# Turbidity_V2.net
KiCad netlist of a schematic drawn in Altium Designer
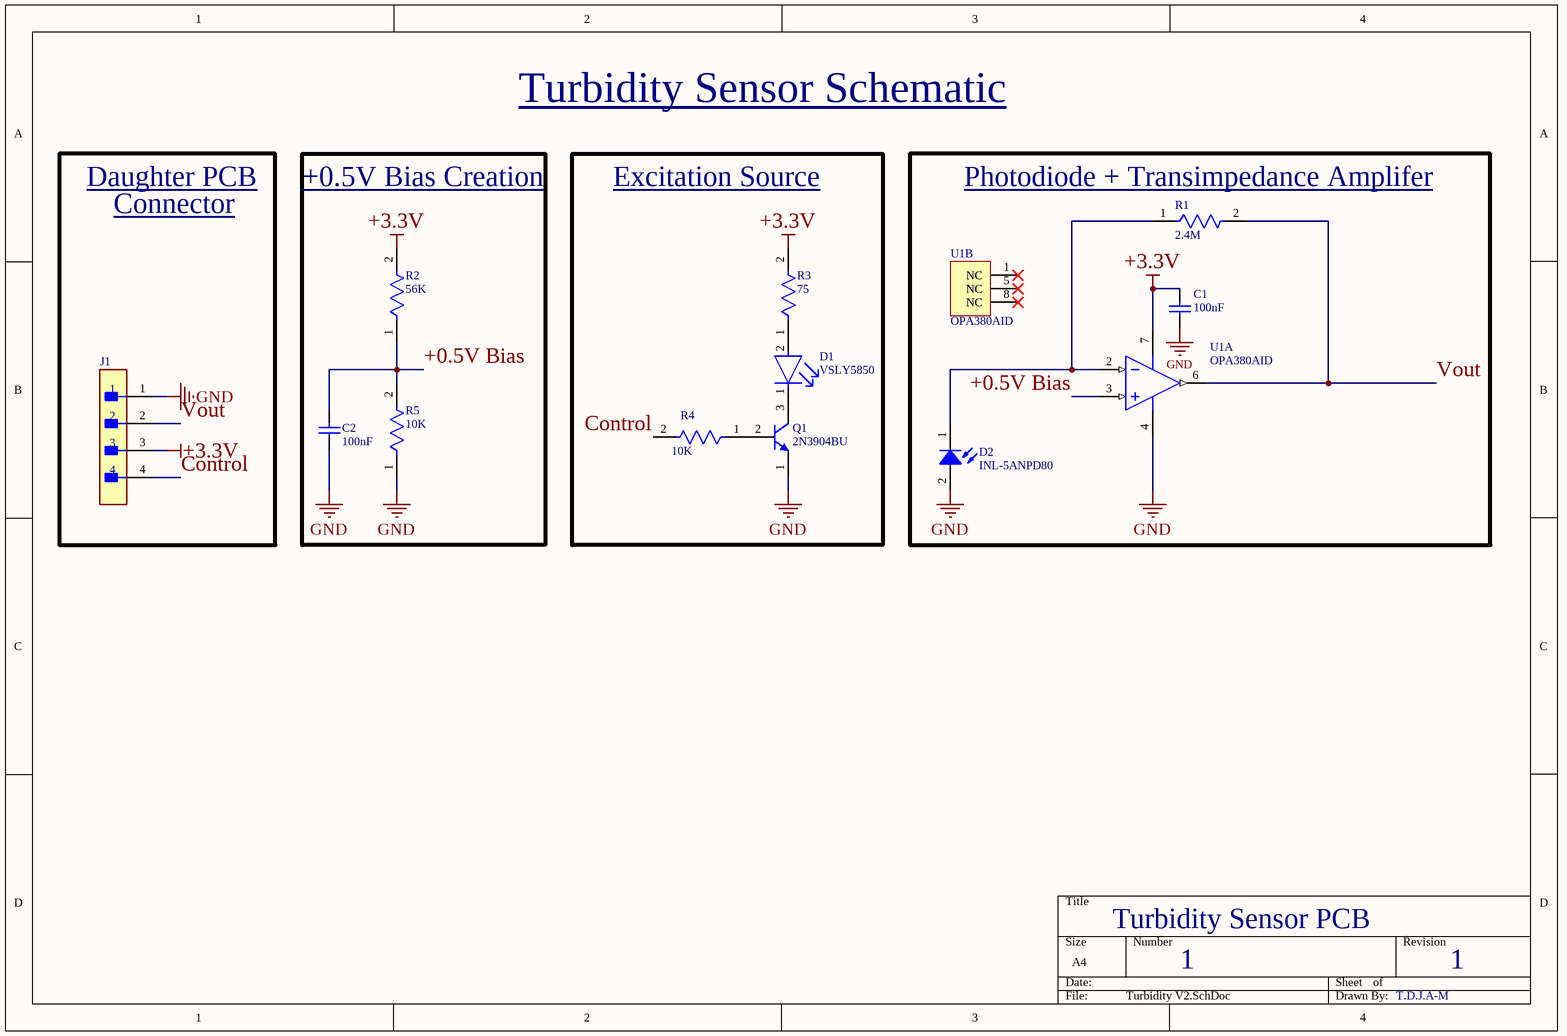
[diagram p0: Turbidity V2.SchDoc]

(export (version "E")
  (design (tool "Eeschema 10.0.6"))
  (components
    (comp (ref "C1")
      (value "100nF")
      (footprint "CAPC2013X145X48ML20T23")
      (fields (field (name "MANUFACTURER") "Vitramon") (field (name "PART NUMBER") "VJ0805Y682KXAMT"))
      (libsource (lib "Altium Content Vault") (part "CAP"))
    )
    (comp (ref "C2")
      (value "100nF")
      (footprint "CAPC2013X145X48ML20T23")
      (fields (field (name "MANUFACTURER") "Vitramon") (field (name "PART NUMBER") "VJ0805Y682KXAMT"))
      (libsource (lib "Altium Content Vault") (part "CAP"))
    )
    (comp (ref "D1")
      (value "VSLY5850")
      (footprint "FP-XLUR12D-MFG")
      (description "627nm Red LED; 5x8.6mm, Through-Hole Mount with Red Diffused Round Lamp")
      (libsource (lib "Altium Content Vault") (part "XLUR12D"))
    )
    (comp (ref "D2")
      (value "INL-5ANPD80")
      (footprint "WL-TDRW_D5.8H8.7")
      (description "1540051EA3590 WL-TDRW THT Photodiode Round Waterclear")
      (libsource (lib "Altium Content Vault") (part "Photodiode"))
    )
    (comp (ref "J1")
      (value "~")
      (footprint "FP-22-29-2041-MFG")
      (description "CONN HEADER VERT 4POS 2.54MM")
      (libsource (lib "Altium Content Vault") (part "299a8cea1bdcbc3624fe62c390fa72c"))
    )
    (comp (ref "Q1")
      (value "2N3904BU")
      (footprint "FAIR-TO-92")
      (description "NPN General-Purpose Amplifier, 40 V VCEO, 0.2 A, -55 to 150 degC, 2-Pin TO-92, RoHS, Bulk")
      (fields (field (name "MANUFACTURER") "FairchildSemiconductor"))
      (libsource (lib "Altium Content Vault") (part "NPN-E1B2C3-3"))
    )
    (comp (ref "R1")
      (value "2.4M")
      (footprint "FP-RT0805-IPC_A")
      (description "RES SMD 681 OHM 0.1% 1/8W 0805")
      (fields
        (field (name "MANUFACTURER") "Yageo")
        (field (name "MANUFACTURER PART NUMBER") "RT0805BRD07681RL")
      )
      (libsource (lib "Altium Content Vault") (part "1029c3af85768c4190bb7ad29bc67b5"))
    )
    (comp (ref "R2")
      (value "56K")
      (footprint "FP-RT0805-IPC_A")
      (description "RES SMD 681 OHM 0.1% 1/8W 0805")
      (fields
        (field (name "MANUFACTURER") "Yageo")
        (field (name "MANUFACTURER PART NUMBER") "RT0805BRD07681RL")
      )
      (libsource (lib "Altium Content Vault") (part "1029c3af85768c4190bb7ad29bc67b5"))
    )
    (comp (ref "R3")
      (value "75")
      (footprint "FP-RT0805-IPC_A")
      (description "RES SMD 681 OHM 0.1% 1/8W 0805")
      (fields
        (field (name "MANUFACTURER") "Yageo")
        (field (name "MANUFACTURER PART NUMBER") "RT0805BRD07681RL")
      )
      (libsource (lib "Altium Content Vault") (part "1029c3af85768c4190bb7ad29bc67b5"))
    )
    (comp (ref "R4")
      (value "10K")
      (footprint "FP-RT0805-IPC_A")
      (description "RES SMD 681 OHM 0.1% 1/8W 0805")
      (fields
        (field (name "MANUFACTURER") "Yageo")
        (field (name "MANUFACTURER PART NUMBER") "RT0805BRD07681RL")
      )
      (libsource (lib "Altium Content Vault") (part "1029c3af85768c4190bb7ad29bc67b5"))
    )
    (comp (ref "R5")
      (value "10K")
      (footprint "FP-RT0805-IPC_A")
      (description "RES SMD 681 OHM 0.1% 1/8W 0805")
      (fields
        (field (name "MANUFACTURER") "Yageo")
        (field (name "MANUFACTURER PART NUMBER") "RT0805BRD07681RL")
      )
      (libsource (lib "Altium Content Vault") (part "1029c3af85768c4190bb7ad29bc67b5"))
    )
    (comp (ref "U1")
      (value "OPA380AID")
      (footprint "D0008A_L")
      (fields (field (name "MANUFACTURER") "Texas Instruments"))
      (libsource (lib "Altium Content Vault") (part "TI-AMP-S3-2-8_B"))
    )
  )
  (nets
    (net (code "1") (name "+3.3V") (class "Default")
      (node (ref "C1") (pin "2") (pinfunction "2_2") (pintype "passive"))
      (node (ref "J1") (pin "3") (pinfunction "3_3") (pintype "passive"))
      (node (ref "R2") (pin "2") (pinfunction "2_2") (pintype "passive"))
      (node (ref "R3") (pin "2") (pinfunction "2_2") (pintype "passive"))
      (node (ref "U1") (pin "7") (pinfunction "V+_7") (pintype "power_in"))
    )
    (net (code "2") (name "/+0.5V Bias") (class "Default")
      (node (ref "C2") (pin "2") (pinfunction "2_2") (pintype "passive"))
      (node (ref "R2") (pin "1") (pinfunction "1_1") (pintype "passive"))
      (node (ref "R5") (pin "2") (pinfunction "2_2") (pintype "passive"))
      (node (ref "U1") (pin "3") (pinfunction "IN+_3") (pintype "input"))
    )
    (net (code "3") (name "/Control") (class "Default")
      (node (ref "J1") (pin "4") (pinfunction "4_4") (pintype "passive"))
      (node (ref "R4") (pin "2") (pinfunction "2_2") (pintype "passive"))
    )
    (net (code "4") (name "/Vout") (class "Default")
      (node (ref "J1") (pin "2") (pinfunction "2_2") (pintype "passive"))
      (node (ref "R1") (pin "2") (pinfunction "2_2") (pintype "passive"))
      (node (ref "U1") (pin "6") (pinfunction "OUT_6") (pintype "output"))
    )
    (net (code "5") (name "GND") (class "Default")
      (node (ref "C1") (pin "1") (pinfunction "1_1") (pintype "passive"))
      (node (ref "C2") (pin "1") (pinfunction "1_1") (pintype "passive"))
      (node (ref "D2") (pin "2") (pinfunction "A_2") (pintype "passive"))
      (node (ref "J1") (pin "1") (pinfunction "1_1") (pintype "passive"))
      (node (ref "Q1") (pin "1") (pinfunction "E_1") (pintype "passive"))
      (node (ref "R5") (pin "1") (pinfunction "1_1") (pintype "passive"))
      (node (ref "U1") (pin "4") (pinfunction "V-_4") (pintype "power_in"))
    )
    (net (code "6") (name "Net-(D1-A)") (class "Default")
      (node (ref "D1") (pin "2") (pinfunction "A_2") (pintype "passive"))
      (node (ref "R3") (pin "1") (pinfunction "1_1") (pintype "passive"))
    )
    (net (code "7") (name "Net-(D1-C)") (class "Default")
      (node (ref "D1") (pin "1") (pinfunction "C_1") (pintype "passive"))
      (node (ref "Q1") (pin "3") (pinfunction "C_3") (pintype "passive"))
    )
    (net (code "8") (name "Net-(D2-K)") (class "Default")
      (node (ref "D2") (pin "1") (pinfunction "K_1") (pintype "passive"))
      (node (ref "R1") (pin "1") (pinfunction "1_1") (pintype "passive"))
      (node (ref "U1") (pin "2") (pinfunction "IN-_2") (pintype "input"))
    )
    (net (code "9") (name "Net-(Q1-B)") (class "Default")
      (node (ref "Q1") (pin "2") (pinfunction "B_2") (pintype "passive"))
      (node (ref "R4") (pin "1") (pinfunction "1_1") (pintype "passive"))
    )
    (net (code "10") (name "unconnected-(U1B-NC-Pad1)") (class "Default")
      (node (ref "U1") (pin "1") (pinfunction "NC_1") (pintype "passive+no_connect"))
    )
    (net (code "11") (name "unconnected-(U1B-NC-Pad5)") (class "Default")
      (node (ref "U1") (pin "5") (pinfunction "NC_5") (pintype "passive+no_connect"))
    )
    (net (code "12") (name "unconnected-(U1B-NC-Pad8)") (class "Default")
      (node (ref "U1") (pin "8") (pinfunction "NC_8") (pintype "passive+no_connect"))
    )
  )
)
